# LO_Distribution.net
KiCad netlist of a schematic drawn in Altium Designer
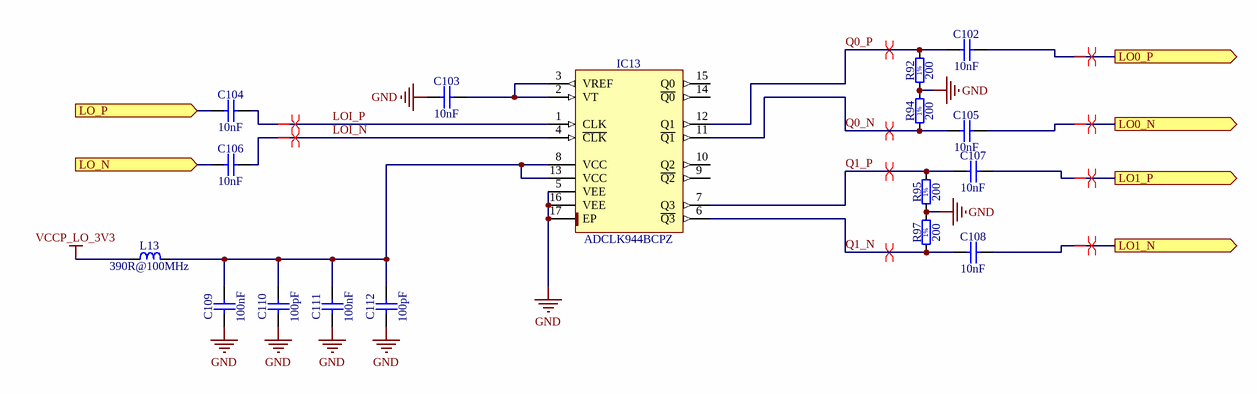
[diagram p0: LO_Distribution.SchDoc]

(export (version "E")
  (design (tool "Eeschema 10.0.6"))
  (components
    (comp (ref "C102")
      (value "10nF")
      (footprint "CAPC1005X55N")
      (description "Non-polarised capacitor")
      (fields
        (field (name "PART NUMBER") "CC0402_10NF_16V_10%_X7R")
        (field (name "VOLTAGE") "16V")
        (field (name "AUTHOR") "CERN DEM JLC")
      )
      (libsource (lib "Capacitors") (part "Capacitor - non polarized"))
    )
    (comp (ref "C103")
      (value "10nF")
      (footprint "CAPC1005X55N")
      (description "Non-polarised capacitor")
      (fields
        (field (name "PART NUMBER") "CC0402_10NF_16V_10%_X7R")
        (field (name "VOLTAGE") "16V")
        (field (name "AUTHOR") "CERN DEM JLC")
      )
      (libsource (lib "Capacitors") (part "Capacitor - non polarized"))
    )
    (comp (ref "C104")
      (value "10nF")
      (footprint "CAPC1005X55N")
      (description "Non-polarised capacitor")
      (fields
        (field (name "PART NUMBER") "CC0402_10NF_16V_10%_X7R")
        (field (name "VOLTAGE") "16V")
        (field (name "AUTHOR") "CERN DEM JLC")
      )
      (libsource (lib "Capacitors") (part "Capacitor - non polarized"))
    )
    (comp (ref "C105")
      (value "10nF")
      (footprint "CAPC1005X55N")
      (description "Non-polarised capacitor")
      (fields
        (field (name "PART NUMBER") "CC0402_10NF_16V_10%_X7R")
        (field (name "VOLTAGE") "16V")
        (field (name "AUTHOR") "CERN DEM JLC")
      )
      (libsource (lib "Capacitors") (part "Capacitor - non polarized"))
    )
    (comp (ref "C106")
      (value "10nF")
      (footprint "CAPC1005X55N")
      (description "Non-polarised capacitor")
      (fields
        (field (name "PART NUMBER") "CC0402_10NF_16V_10%_X7R")
        (field (name "VOLTAGE") "16V")
        (field (name "AUTHOR") "CERN DEM JLC")
      )
      (libsource (lib "Capacitors") (part "Capacitor - non polarized"))
    )
    (comp (ref "C107")
      (value "10nF")
      (footprint "CAPC1005X55N")
      (description "Non-polarised capacitor")
      (fields
        (field (name "PART NUMBER") "CC0402_10NF_16V_10%_X7R")
        (field (name "VOLTAGE") "16V")
        (field (name "AUTHOR") "CERN DEM JLC")
      )
      (libsource (lib "Capacitors") (part "Capacitor - non polarized"))
    )
    (comp (ref "C108")
      (value "10nF")
      (footprint "CAPC1005X55N")
      (description "Non-polarised capacitor")
      (fields
        (field (name "PART NUMBER") "CC0402_10NF_16V_10%_X7R")
        (field (name "VOLTAGE") "16V")
        (field (name "AUTHOR") "CERN DEM JLC")
      )
      (libsource (lib "Capacitors") (part "Capacitor - non polarized"))
    )
    (comp (ref "C109")
      (value "100nF")
      (footprint "CAPC1005X55N")
      (description "Non-polarised capacitor")
      (fields
        (field (name "PART NUMBER") "CC0402_100NF_16V_10%_X7R")
        (field (name "VOLTAGE") "16V")
        (field (name "AUTHOR") "CERN DEM JLC")
      )
      (libsource (lib "Capacitors") (part "Capacitor - non polarized"))
    )
    (comp (ref "C110")
      (value "100pF")
      (footprint "CAPC1005X55N")
      (description "Non-polarised capacitor")
      (fields
        (field (name "PART NUMBER") "CC0402_100PF_50V_5%_C0G")
        (field (name "VOLTAGE") "50V")
        (field (name "AUTHOR") "CERN DEM JLC")
      )
      (libsource (lib "Capacitors") (part "Capacitor - non polarized"))
    )
    (comp (ref "C111")
      (value "100nF")
      (footprint "CAPC1005X55N")
      (description "Non-polarised capacitor")
      (fields
        (field (name "PART NUMBER") "CC0402_100NF_16V_10%_X7R")
        (field (name "VOLTAGE") "16V")
        (field (name "AUTHOR") "CERN DEM JLC")
      )
      (libsource (lib "Capacitors") (part "Capacitor - non polarized"))
    )
    (comp (ref "C112")
      (value "100pF")
      (footprint "CAPC1005X55N")
      (description "Non-polarised capacitor")
      (fields
        (field (name "PART NUMBER") "CC0402_100PF_50V_5%_C0G")
        (field (name "VOLTAGE") "50V")
        (field (name "AUTHOR") "CERN DEM JLC")
      )
      (libsource (lib "Capacitors") (part "Capacitor - non polarized"))
    )
    (comp (ref "IC13")
      (value "ADCLK944BCPZ")
      (footprint "QFN50P300X300X80-17N-S160")
      (description "2.5V/3.3V, Four LVPECL Outputs, SiGe Clock Fanout Buffer")
      (fields (field (name "MANUFACTURER") "ANALOG DEVICES") (field (name "AUTHOR") "CERN DEM JLC"))
      (libsource (lib "ICs And Semiconductors") (part "ADCLK944"))
    )
    (comp (ref "L13")
      (value "390R@100MHz")
      (footprint "INDC1608X95N")
      (description "Inductor")
      (fields
        (field (name "PART NUMBER") "IND0603_TDK_MPZ1608R391A")
        (field (name "POWER") "1.2A")
        (field (name "AUTHOR") "CERN DEM JLC")
      )
      (libsource (lib "Inductors & Transformers") (part "Inductor"))
    )
    (comp (ref "R92")
      (value "200")
      (footprint "RESC1005X40N")
      (description "Resistor - 1%")
      (fields
        (field (name "PART NUMBER") "R0402_200R_1%_0.0625W_100PPM")
        (field (name "POWER") "0.0625W")
        (field (name "AUTHOR") "CERN DEM JLC")
      )
      (libsource (lib "Resistors") (part "Resistor - 1%"))
    )
    (comp (ref "R94")
      (value "200")
      (footprint "RESC1005X40N")
      (description "Resistor - 1%")
      (fields
        (field (name "PART NUMBER") "R0402_200R_1%_0.0625W_100PPM")
        (field (name "POWER") "0.0625W")
        (field (name "AUTHOR") "CERN DEM JLC")
      )
      (libsource (lib "Resistors") (part "Resistor - 1%"))
    )
    (comp (ref "R95")
      (value "200")
      (footprint "RESC1005X40N")
      (description "Resistor - 1%")
      (fields
        (field (name "PART NUMBER") "R0402_200R_1%_0.0625W_100PPM")
        (field (name "POWER") "0.0625W")
        (field (name "AUTHOR") "CERN DEM JLC")
      )
      (libsource (lib "Resistors") (part "Resistor - 1%"))
    )
    (comp (ref "R97")
      (value "200")
      (footprint "RESC1005X40N")
      (description "Resistor - 1%")
      (fields
        (field (name "PART NUMBER") "R0402_200R_1%_0.0625W_100PPM")
        (field (name "POWER") "0.0625W")
        (field (name "AUTHOR") "CERN DEM JLC")
      )
      (libsource (lib "Resistors") (part "Resistor - 1%"))
    )
  )
  (nets
    (net (code "1") (name "/LO0_N") (class "Default")
      (node (ref "C105") (pin "2") (pinfunction "2_2") (pintype "passive"))
    )
    (net (code "2") (name "/LO0_P") (class "Default")
      (node (ref "C102") (pin "2") (pinfunction "2_2") (pintype "passive"))
    )
    (net (code "3") (name "/LO1_N") (class "Default")
      (node (ref "C108") (pin "2") (pinfunction "2_2") (pintype "passive"))
    )
    (net (code "4") (name "/LO1_P") (class "Default")
      (node (ref "C107") (pin "2") (pinfunction "2_2") (pintype "passive"))
    )
    (net (code "5") (name "/LOI_N") (class "Default")
      (node (ref "C106") (pin "2") (pinfunction "2_2") (pintype "passive"))
      (node (ref "IC13") (pin "4") (pinfunction "~{CLK}_4") (pintype "input"))
    )
    (net (code "6") (name "/LOI_P") (class "Default")
      (node (ref "C104") (pin "2") (pinfunction "2_2") (pintype "passive"))
      (node (ref "IC13") (pin "1") (pinfunction "CLK_1") (pintype "input"))
    )
    (net (code "7") (name "/LO_N") (class "Default")
      (node (ref "C106") (pin "1") (pinfunction "1_1") (pintype "passive"))
    )
    (net (code "8") (name "/LO_P") (class "Default")
      (node (ref "C104") (pin "1") (pinfunction "1_1") (pintype "passive"))
    )
    (net (code "9") (name "/Q0_N") (class "Default")
      (node (ref "C105") (pin "1") (pinfunction "1_1") (pintype "passive"))
      (node (ref "IC13") (pin "11") (pinfunction "~{Q1}_11") (pintype "output"))
      (node (ref "R94") (pin "1") (pinfunction "1_1") (pintype "passive"))
    )
    (net (code "10") (name "/Q0_P") (class "Default")
      (node (ref "C102") (pin "1") (pinfunction "1_1") (pintype "passive"))
      (node (ref "IC13") (pin "12") (pinfunction "Q1_12") (pintype "output"))
      (node (ref "R92") (pin "2") (pinfunction "2_2") (pintype "passive"))
    )
    (net (code "11") (name "/Q1_N") (class "Default")
      (node (ref "C108") (pin "1") (pinfunction "1_1") (pintype "passive"))
      (node (ref "IC13") (pin "6") (pinfunction "~{Q3}_6") (pintype "output"))
      (node (ref "R97") (pin "1") (pinfunction "1_1") (pintype "passive"))
    )
    (net (code "12") (name "/Q1_P") (class "Default")
      (node (ref "C107") (pin "1") (pinfunction "1_1") (pintype "passive"))
      (node (ref "IC13") (pin "7") (pinfunction "Q3_7") (pintype "output"))
      (node (ref "R95") (pin "2") (pinfunction "2_2") (pintype "passive"))
    )
    (net (code "13") (name "GND") (class "Default")
      (node (ref "C103") (pin "1") (pinfunction "1_1") (pintype "passive"))
      (node (ref "C109") (pin "1") (pinfunction "1_1") (pintype "passive"))
      (node (ref "C110") (pin "1") (pinfunction "1_1") (pintype "passive"))
      (node (ref "C111") (pin "1") (pinfunction "1_1") (pintype "passive"))
      (node (ref "C112") (pin "1") (pinfunction "1_1") (pintype "passive"))
      (node (ref "IC13") (pin "16") (pinfunction "VEE_16") (pintype "power_in"))
      (node (ref "IC13") (pin "17") (pinfunction "EP_17") (pintype "power_in"))
      (node (ref "IC13") (pin "5") (pinfunction "VEE_5") (pintype "power_in"))
      (node (ref "R92") (pin "1") (pinfunction "1_1") (pintype "passive"))
      (node (ref "R94") (pin "2") (pinfunction "2_2") (pintype "passive"))
      (node (ref "R95") (pin "1") (pinfunction "1_1") (pintype "passive"))
      (node (ref "R97") (pin "2") (pinfunction "2_2") (pintype "passive"))
    )
    (net (code "14") (name "Net-(C109-Pad2)") (class "Default")
      (node (ref "C109") (pin "2") (pinfunction "2_2") (pintype "passive"))
      (node (ref "C110") (pin "2") (pinfunction "2_2") (pintype "passive"))
      (node (ref "C111") (pin "2") (pinfunction "2_2") (pintype "passive"))
      (node (ref "C112") (pin "2") (pinfunction "2_2") (pintype "passive"))
      (node (ref "IC13") (pin "13") (pinfunction "VCC_13") (pintype "power_in"))
      (node (ref "IC13") (pin "8") (pinfunction "VCC_8") (pintype "power_in"))
      (node (ref "L13") (pin "2") (pinfunction "2_2") (pintype "passive"))
    )
    (net (code "15") (name "Net-(IC13-VREF)") (class "Default")
      (node (ref "C103") (pin "2") (pinfunction "2_2") (pintype "passive"))
      (node (ref "IC13") (pin "2") (pinfunction "VT_2") (pintype "input"))
      (node (ref "IC13") (pin "3") (pinfunction "VREF_3") (pintype "output"))
    )
    (net (code "16") (name "VCCP_LO_3V3") (class "Default")
      (node (ref "L13") (pin "1") (pinfunction "1_1") (pintype "passive"))
    )
    (net (code "17") (name "unconnected-(IC13-Q0-Pad15)") (class "Default")
      (node (ref "IC13") (pin "15") (pinfunction "Q0_15") (pintype "output"))
    )
    (net (code "18") (name "unconnected-(IC13-Q2-Pad10)") (class "Default")
      (node (ref "IC13") (pin "10") (pinfunction "Q2_10") (pintype "output"))
    )
    (net (code "19") (name "unconnected-(IC13-~{Q0}-Pad14)") (class "Default")
      (node (ref "IC13") (pin "14") (pinfunction "~{Q0}_14") (pintype "output"))
    )
    (net (code "20") (name "unconnected-(IC13-~{Q2}-Pad9)") (class "Default")
      (node (ref "IC13") (pin "9") (pinfunction "~{Q2}_9") (pintype "output"))
    )
  )
)
